# CBM_TAPE_PI.net
KiCad netlist of a schematic drawn in EAGLE
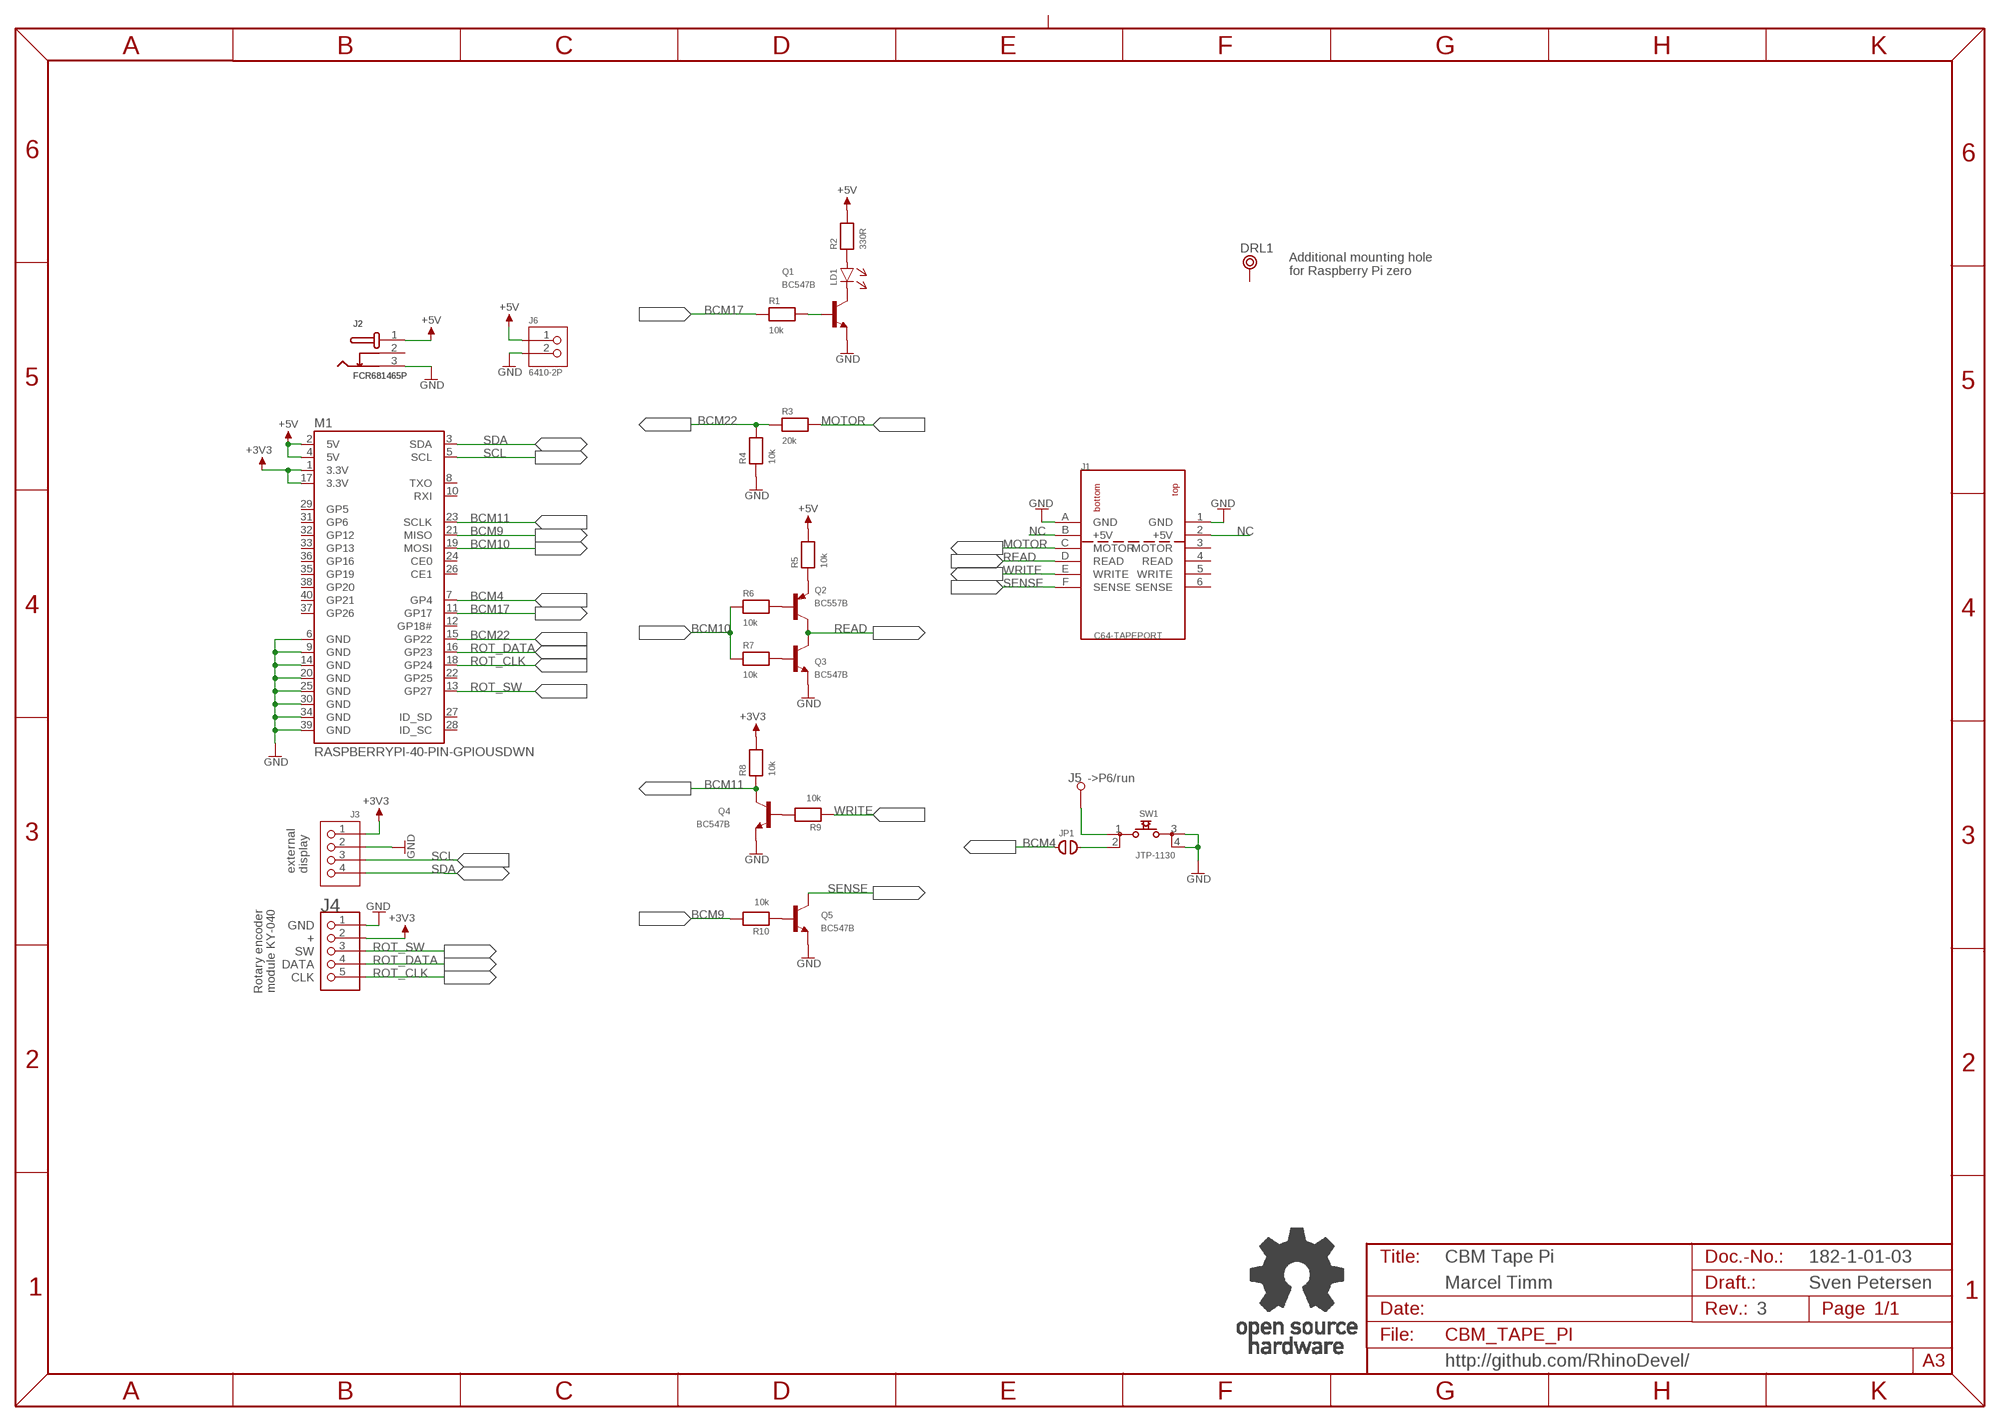
[diagram p0: schematic, sheet 1]

(export (version "E")
  (design (tool "Eeschema 10.0.6"))
  (components
    (comp (ref "DRL1")
      (value "RPI_MNT")
      (footprint "eagle-import:RASPI_MNT")
      (libsource (lib "eagle-import") (part "RPI_MNT"))
    )
    (comp (ref "J1")
      (value "C64-TAPEPORT")
      (footprint "eagle-import:TAPEPORT")
      (libsource (lib "eagle-import") (part "C64-TAPEPORT"))
    )
    (comp (ref "J2")
      (value "FCR681465P")
      (footprint "eagle-import:FCR681465P")
      (libsource (lib "eagle-import") (part "FCR681465P"))
    )
    (comp (ref "J3")
      (value "6410-4P")
      (footprint "eagle-import:6410-4P")
      (libsource (lib "eagle-import") (part "6410-4P"))
    )
    (comp (ref "J4")
      (value "6410-5P")
      (footprint "eagle-import:6410-5P")
      (libsource (lib "eagle-import") (part "6410-5P"))
    )
    (comp (ref "J5")
      (value "L1,2_R")
      (footprint "eagle-import:1,2MM_R")
      (libsource (lib "eagle-import") (part "L1,2_R"))
    )
    (comp (ref "J6")
      (value "6410-2P")
      (footprint "eagle-import:6410-2P")
      (libsource (lib "eagle-import") (part "6410-2P"))
    )
    (comp (ref "JP1")
      (value "OPEN")
      (footprint "eagle-import:CP_OP")
      (libsource (lib "eagle-import") (part "OPEN"))
    )
    (comp (ref "LD1")
      (value "3MM")
      (footprint "eagle-import:3MM")
      (libsource (lib "eagle-import") (part "3MM"))
    )
    (comp (ref "M1")
      (value "RASPBERRYPI-40-PIN-GPIOUSDWN")
      (footprint "eagle-import:PI_HAT_40P_UPSIDEDOWN")
      (libsource (lib "eagle-import") (part "RASPBERRYPI-40-PIN-GPIOUSDWN"))
    )
    (comp (ref "Q1")
      (value "BC547B")
      (footprint "eagle-import:TO92")
      (libsource (lib "eagle-import") (part "BC547B"))
    )
    (comp (ref "Q2")
      (value "BC557B")
      (footprint "eagle-import:TO92-EBC")
      (libsource (lib "eagle-import") (part "BC557B"))
    )
    (comp (ref "Q3")
      (value "BC547B")
      (footprint "eagle-import:TO92")
      (libsource (lib "eagle-import") (part "BC547B"))
    )
    (comp (ref "Q4")
      (value "BC547B")
      (footprint "eagle-import:TO92")
      (libsource (lib "eagle-import") (part "BC547B"))
    )
    (comp (ref "Q5")
      (value "BC547B")
      (footprint "eagle-import:TO92")
      (libsource (lib "eagle-import") (part "BC547B"))
    )
    (comp (ref "R1")
      (value "10k")
      (footprint "eagle-import:R-10")
      (libsource (lib "eagle-import") (part "RES04"))
    )
    (comp (ref "R2")
      (value "330R")
      (footprint "eagle-import:R-10")
      (libsource (lib "eagle-import") (part "RES04"))
    )
    (comp (ref "R3")
      (value "20k")
      (footprint "eagle-import:R-10")
      (libsource (lib "eagle-import") (part "RES04"))
    )
    (comp (ref "R4")
      (value "10k")
      (footprint "eagle-import:R-10")
      (libsource (lib "eagle-import") (part "RES04"))
    )
    (comp (ref "R5")
      (value "10k")
      (footprint "eagle-import:R-10")
      (libsource (lib "eagle-import") (part "RES04"))
    )
    (comp (ref "R6")
      (value "10k")
      (footprint "eagle-import:R-10")
      (libsource (lib "eagle-import") (part "RES04"))
    )
    (comp (ref "R7")
      (value "10k")
      (footprint "eagle-import:R-10")
      (libsource (lib "eagle-import") (part "RES04"))
    )
    (comp (ref "R8")
      (value "10k")
      (footprint "eagle-import:R-10")
      (libsource (lib "eagle-import") (part "RES04"))
    )
    (comp (ref "R9")
      (value "10k")
      (footprint "eagle-import:R-10")
      (libsource (lib "eagle-import") (part "RES04"))
    )
    (comp (ref "R10")
      (value "10k")
      (footprint "eagle-import:R-10")
      (libsource (lib "eagle-import") (part "RES04"))
    )
    (comp (ref "SW1")
      (value "JTP-1130")
      (footprint "eagle-import:JTP-1130")
      (libsource (lib "eagle-import") (part "JTP-1130"))
    )
    (comp (ref "U$2")
      (value "OPEN_SOURCE_HW")
      (footprint "eagle-import:OPENHW")
      (libsource (lib "eagle-import") (part "OPEN_SOURCE_HW"))
    )
  )
  (nets
    (net (code "1") (name "+3V3") (class "Default")
      (node (ref "J3") (pin "1") (pinfunction "1_1") (pintype "passive"))
      (node (ref "J4") (pin "2") (pinfunction "2_2") (pintype "passive"))
      (node (ref "M1") (pin "1") (pinfunction "3.3V_1") (pintype "power_in"))
      (node (ref "M1") (pin "17") (pinfunction "3.3V_17") (pintype "power_in"))
      (node (ref "R8") (pin "2") (pinfunction "2_2") (pintype "passive"))
    )
    (net (code "2") (name "+5V") (class "Default")
      (node (ref "J2") (pin "1") (pinfunction "1_1") (pintype "bidirectional"))
      (node (ref "J6") (pin "1") (pinfunction "1_1") (pintype "passive"))
      (node (ref "M1") (pin "2") (pinfunction "5V_2") (pintype "power_in"))
      (node (ref "M1") (pin "4") (pinfunction "5V_4") (pintype "power_in"))
      (node (ref "R2") (pin "2") (pinfunction "2_2") (pintype "passive"))
      (node (ref "R5") (pin "2") (pinfunction "2_2") (pintype "passive"))
    )
    (net (code "3") (name "/BCM4") (class "Default")
      (node (ref "JP1") (pin "1") (pinfunction "1_1") (pintype "passive"))
      (node (ref "M1") (pin "7") (pinfunction "GP4_7") (pintype "bidirectional"))
    )
    (net (code "4") (name "/BCM9") (class "Default")
      (node (ref "M1") (pin "21") (pinfunction "MISO_21") (pintype "input"))
      (node (ref "R10") (pin "2") (pinfunction "2_2") (pintype "passive"))
    )
    (net (code "5") (name "/BCM10") (class "Default")
      (node (ref "M1") (pin "19") (pinfunction "MOSI_19") (pintype "output"))
      (node (ref "R6") (pin "1") (pinfunction "1_1") (pintype "passive"))
      (node (ref "R7") (pin "1") (pinfunction "1_1") (pintype "passive"))
    )
    (net (code "6") (name "/BCM11") (class "Default")
      (node (ref "M1") (pin "23") (pinfunction "SCLK_23") (pintype "output"))
      (node (ref "Q4") (pin "3") (pinfunction "C_3") (pintype "passive"))
      (node (ref "R8") (pin "1") (pinfunction "1_1") (pintype "passive"))
    )
    (net (code "7") (name "/BCM17") (class "Default")
      (node (ref "M1") (pin "11") (pinfunction "GP17_11") (pintype "bidirectional"))
      (node (ref "R1") (pin "1") (pinfunction "1_1") (pintype "passive"))
    )
    (net (code "8") (name "/BCM22") (class "Default")
      (node (ref "M1") (pin "15") (pinfunction "GP22_15") (pintype "bidirectional"))
      (node (ref "R3") (pin "1") (pinfunction "1_1") (pintype "passive"))
      (node (ref "R4") (pin "2") (pinfunction "2_2") (pintype "passive"))
    )
    (net (code "9") (name "/MOTOR") (class "Default")
      (node (ref "J1") (pin "C") (pinfunction "MOTOR_C") (pintype "output"))
      (node (ref "R3") (pin "2") (pinfunction "2_2") (pintype "passive"))
    )
    (net (code "10") (name "/NC") (class "Default")
      (node (ref "J1") (pin "2") (pinfunction "+5V_2") (pintype "power_in"))
      (node (ref "J1") (pin "B") (pinfunction "+5V_B") (pintype "power_in"))
    )
    (net (code "11") (name "/READ") (class "Default")
      (node (ref "J1") (pin "D") (pinfunction "READ_D") (pintype "input"))
      (node (ref "Q2") (pin "C") (pinfunction "C_C") (pintype "passive"))
      (node (ref "Q3") (pin "3") (pinfunction "C_3") (pintype "passive"))
    )
    (net (code "12") (name "/ROT_CLK") (class "Default")
      (node (ref "J4") (pin "5") (pinfunction "5_5") (pintype "passive"))
      (node (ref "M1") (pin "18") (pinfunction "GP24_18") (pintype "bidirectional"))
    )
    (net (code "13") (name "/ROT_DATA") (class "Default")
      (node (ref "J4") (pin "4") (pinfunction "4_4") (pintype "passive"))
      (node (ref "M1") (pin "16") (pinfunction "GP23_16") (pintype "bidirectional"))
    )
    (net (code "14") (name "/ROT_SW") (class "Default")
      (node (ref "J4") (pin "3") (pinfunction "3_3") (pintype "passive"))
      (node (ref "M1") (pin "13") (pinfunction "GP27_13") (pintype "bidirectional"))
    )
    (net (code "15") (name "/SCL") (class "Default")
      (node (ref "J3") (pin "3") (pinfunction "3_3") (pintype "passive"))
      (node (ref "M1") (pin "5") (pinfunction "SCL_5") (pintype "bidirectional"))
    )
    (net (code "16") (name "/SDA") (class "Default")
      (node (ref "J3") (pin "4") (pinfunction "4_4") (pintype "passive"))
      (node (ref "M1") (pin "3") (pinfunction "SDA_3") (pintype "bidirectional"))
    )
    (net (code "17") (name "/SENSE") (class "Default")
      (node (ref "J1") (pin "F") (pinfunction "SENSE_F") (pintype "input"))
      (node (ref "Q5") (pin "3") (pinfunction "C_3") (pintype "passive"))
    )
    (net (code "18") (name "/WRITE") (class "Default")
      (node (ref "J1") (pin "E") (pinfunction "WRITE_E") (pintype "output"))
      (node (ref "R9") (pin "1") (pinfunction "1_1") (pintype "passive"))
    )
    (net (code "19") (name "GND") (class "Default")
      (node (ref "J1") (pin "1") (pinfunction "GND_1") (pintype "power_in"))
      (node (ref "J1") (pin "A") (pinfunction "GND_A") (pintype "power_in"))
      (node (ref "J2") (pin "3") (pinfunction "3_3") (pintype "bidirectional"))
      (node (ref "J3") (pin "2") (pinfunction "2_2") (pintype "passive"))
      (node (ref "J4") (pin "1") (pinfunction "1_1") (pintype "passive"))
      (node (ref "J6") (pin "2") (pinfunction "2_2") (pintype "passive"))
      (node (ref "M1") (pin "14") (pinfunction "GND_14") (pintype "power_in"))
      (node (ref "M1") (pin "20") (pinfunction "GND_20") (pintype "power_in"))
      (node (ref "M1") (pin "25") (pinfunction "GND_25") (pintype "power_in"))
      (node (ref "M1") (pin "30") (pinfunction "GND_30") (pintype "power_in"))
      (node (ref "M1") (pin "34") (pinfunction "GND_34") (pintype "power_in"))
      (node (ref "M1") (pin "39") (pinfunction "GND_39") (pintype "power_in"))
      (node (ref "M1") (pin "6") (pinfunction "GND_6") (pintype "power_in"))
      (node (ref "M1") (pin "9") (pinfunction "GND_9") (pintype "power_in"))
      (node (ref "Q1") (pin "1") (pinfunction "E_1") (pintype "passive"))
      (node (ref "Q3") (pin "1") (pinfunction "E_1") (pintype "passive"))
      (node (ref "Q4") (pin "1") (pinfunction "E_1") (pintype "passive"))
      (node (ref "Q5") (pin "1") (pinfunction "E_1") (pintype "passive"))
      (node (ref "R4") (pin "1") (pinfunction "1_1") (pintype "passive"))
      (node (ref "SW1") (pin "3") (pinfunction "3_3") (pintype "passive"))
      (node (ref "SW1") (pin "4") (pinfunction "4_4") (pintype "passive"))
    )
    (net (code "20") (name "Net-(J5-Pad1)") (class "Default")
      (node (ref "J5") (pin "1") (pinfunction "1_1") (pintype "passive"))
      (node (ref "SW1") (pin "1") (pinfunction "1_1") (pintype "passive"))
    )
    (net (code "21") (name "Net-(JP1-Pad2)") (class "Default")
      (node (ref "JP1") (pin "2") (pinfunction "2_2") (pintype "passive"))
      (node (ref "SW1") (pin "2") (pinfunction "2_2") (pintype "passive"))
    )
    (net (code "22") (name "Net-(LD1-K)") (class "Default")
      (node (ref "LD1") (pin "C") (pinfunction "K_C") (pintype "bidirectional"))
      (node (ref "Q1") (pin "3") (pinfunction "C_3") (pintype "passive"))
    )
    (net (code "23") (name "Net-(LD1-PadA)") (class "Default")
      (node (ref "LD1") (pin "A") (pinfunction "A_A") (pintype "bidirectional"))
      (node (ref "R2") (pin "1") (pinfunction "1_1") (pintype "passive"))
    )
    (net (code "24") (name "Net-(Q1-B)") (class "Default")
      (node (ref "Q1") (pin "2") (pinfunction "B_2") (pintype "passive"))
      (node (ref "R1") (pin "2") (pinfunction "2_2") (pintype "passive"))
    )
    (net (code "25") (name "Net-(Q2-PadB)") (class "Default")
      (node (ref "Q2") (pin "B") (pinfunction "B_B") (pintype "passive"))
      (node (ref "R6") (pin "2") (pinfunction "2_2") (pintype "passive"))
    )
    (net (code "26") (name "Net-(Q2-PadE)") (class "Default")
      (node (ref "Q2") (pin "E") (pinfunction "E_E") (pintype "passive"))
      (node (ref "R5") (pin "1") (pinfunction "1_1") (pintype "passive"))
    )
    (net (code "27") (name "Net-(Q3-B)") (class "Default")
      (node (ref "Q3") (pin "2") (pinfunction "B_2") (pintype "passive"))
      (node (ref "R7") (pin "2") (pinfunction "2_2") (pintype "passive"))
    )
    (net (code "28") (name "Net-(Q4-B)") (class "Default")
      (node (ref "Q4") (pin "2") (pinfunction "B_2") (pintype "passive"))
      (node (ref "R9") (pin "2") (pinfunction "2_2") (pintype "passive"))
    )
    (net (code "29") (name "Net-(Q5-B)") (class "Default")
      (node (ref "Q5") (pin "2") (pinfunction "B_2") (pintype "passive"))
      (node (ref "R10") (pin "1") (pinfunction "1_1") (pintype "passive"))
    )
    (net (code "30") (name "unconnected-(DRL1-P$1-PadMH)") (class "Default")
      (node (ref "DRL1") (pin "MH") (pinfunction "P$1_MH") (pintype "passive"))
    )
    (net (code "31") (name "unconnected-(J1-MOTOR-Pad3)") (class "Default")
      (node (ref "J1") (pin "3") (pinfunction "MOTOR_3") (pintype "output"))
    )
    (net (code "32") (name "unconnected-(J1-READ-Pad4)") (class "Default")
      (node (ref "J1") (pin "4") (pinfunction "READ_4") (pintype "input"))
    )
    (net (code "33") (name "unconnected-(J1-SENSE-Pad6)") (class "Default")
      (node (ref "J1") (pin "6") (pinfunction "SENSE_6") (pintype "input"))
    )
    (net (code "34") (name "unconnected-(J1-WRITE-Pad5)") (class "Default")
      (node (ref "J1") (pin "5") (pinfunction "WRITE_5") (pintype "output"))
    )
    (net (code "35") (name "unconnected-(J2-Pad2)") (class "Default")
      (node (ref "J2") (pin "2") (pinfunction "2_2") (pintype "bidirectional"))
    )
    (net (code "36") (name "unconnected-(M1-CE0-Pad24)") (class "Default")
      (node (ref "M1") (pin "24") (pinfunction "CE0_24") (pintype "output"))
    )
    (net (code "37") (name "unconnected-(M1-CE1-Pad26)") (class "Default")
      (node (ref "M1") (pin "26") (pinfunction "CE1_26") (pintype "output"))
    )
    (net (code "38") (name "unconnected-(M1-GP5-Pad29)") (class "Default")
      (node (ref "M1") (pin "29") (pinfunction "GP5_29") (pintype "bidirectional"))
    )
    (net (code "39") (name "unconnected-(M1-GP6-Pad31)") (class "Default")
      (node (ref "M1") (pin "31") (pinfunction "GP6_31") (pintype "bidirectional"))
    )
    (net (code "40") (name "unconnected-(M1-GP12-Pad32)") (class "Default")
      (node (ref "M1") (pin "32") (pinfunction "GP12_32") (pintype "bidirectional"))
    )
    (net (code "41") (name "unconnected-(M1-GP13-Pad33)") (class "Default")
      (node (ref "M1") (pin "33") (pinfunction "GP13_33") (pintype "bidirectional"))
    )
    (net (code "42") (name "unconnected-(M1-GP16-Pad36)") (class "Default")
      (node (ref "M1") (pin "36") (pinfunction "GP16_36") (pintype "bidirectional"))
    )
    (net (code "43") (name "unconnected-(M1-GP18#-Pad12)") (class "Default")
      (node (ref "M1") (pin "12") (pinfunction "GP18#_12") (pintype "bidirectional"))
    )
    (net (code "44") (name "unconnected-(M1-GP19-Pad35)") (class "Default")
      (node (ref "M1") (pin "35") (pinfunction "GP19_35") (pintype "bidirectional"))
    )
    (net (code "45") (name "unconnected-(M1-GP20-Pad38)") (class "Default")
      (node (ref "M1") (pin "38") (pinfunction "GP20_38") (pintype "bidirectional"))
    )
    (net (code "46") (name "unconnected-(M1-GP21-Pad40)") (class "Default")
      (node (ref "M1") (pin "40") (pinfunction "GP21_40") (pintype "bidirectional"))
    )
    (net (code "47") (name "unconnected-(M1-GP25-Pad22)") (class "Default")
      (node (ref "M1") (pin "22") (pinfunction "GP25_22") (pintype "bidirectional"))
    )
    (net (code "48") (name "unconnected-(M1-GP26-Pad37)") (class "Default")
      (node (ref "M1") (pin "37") (pinfunction "GP26_37") (pintype "bidirectional"))
    )
    (net (code "49") (name "unconnected-(M1-ID_SC-Pad28)") (class "Default")
      (node (ref "M1") (pin "28") (pinfunction "ID_SC_28") (pintype "bidirectional"))
    )
    (net (code "50") (name "unconnected-(M1-ID_SD-Pad27)") (class "Default")
      (node (ref "M1") (pin "27") (pinfunction "ID_SD_27") (pintype "bidirectional"))
    )
    (net (code "51") (name "unconnected-(M1-RXI-Pad10)") (class "Default")
      (node (ref "M1") (pin "10") (pinfunction "RXI_10") (pintype "input"))
    )
    (net (code "52") (name "unconnected-(M1-TXO-Pad8)") (class "Default")
      (node (ref "M1") (pin "8") (pinfunction "TXO_8") (pintype "output"))
    )
  )
)
